# PCB_VIP_Master_BMS_2026.net
KiCad netlist of a schematic drawn in EasyEDA
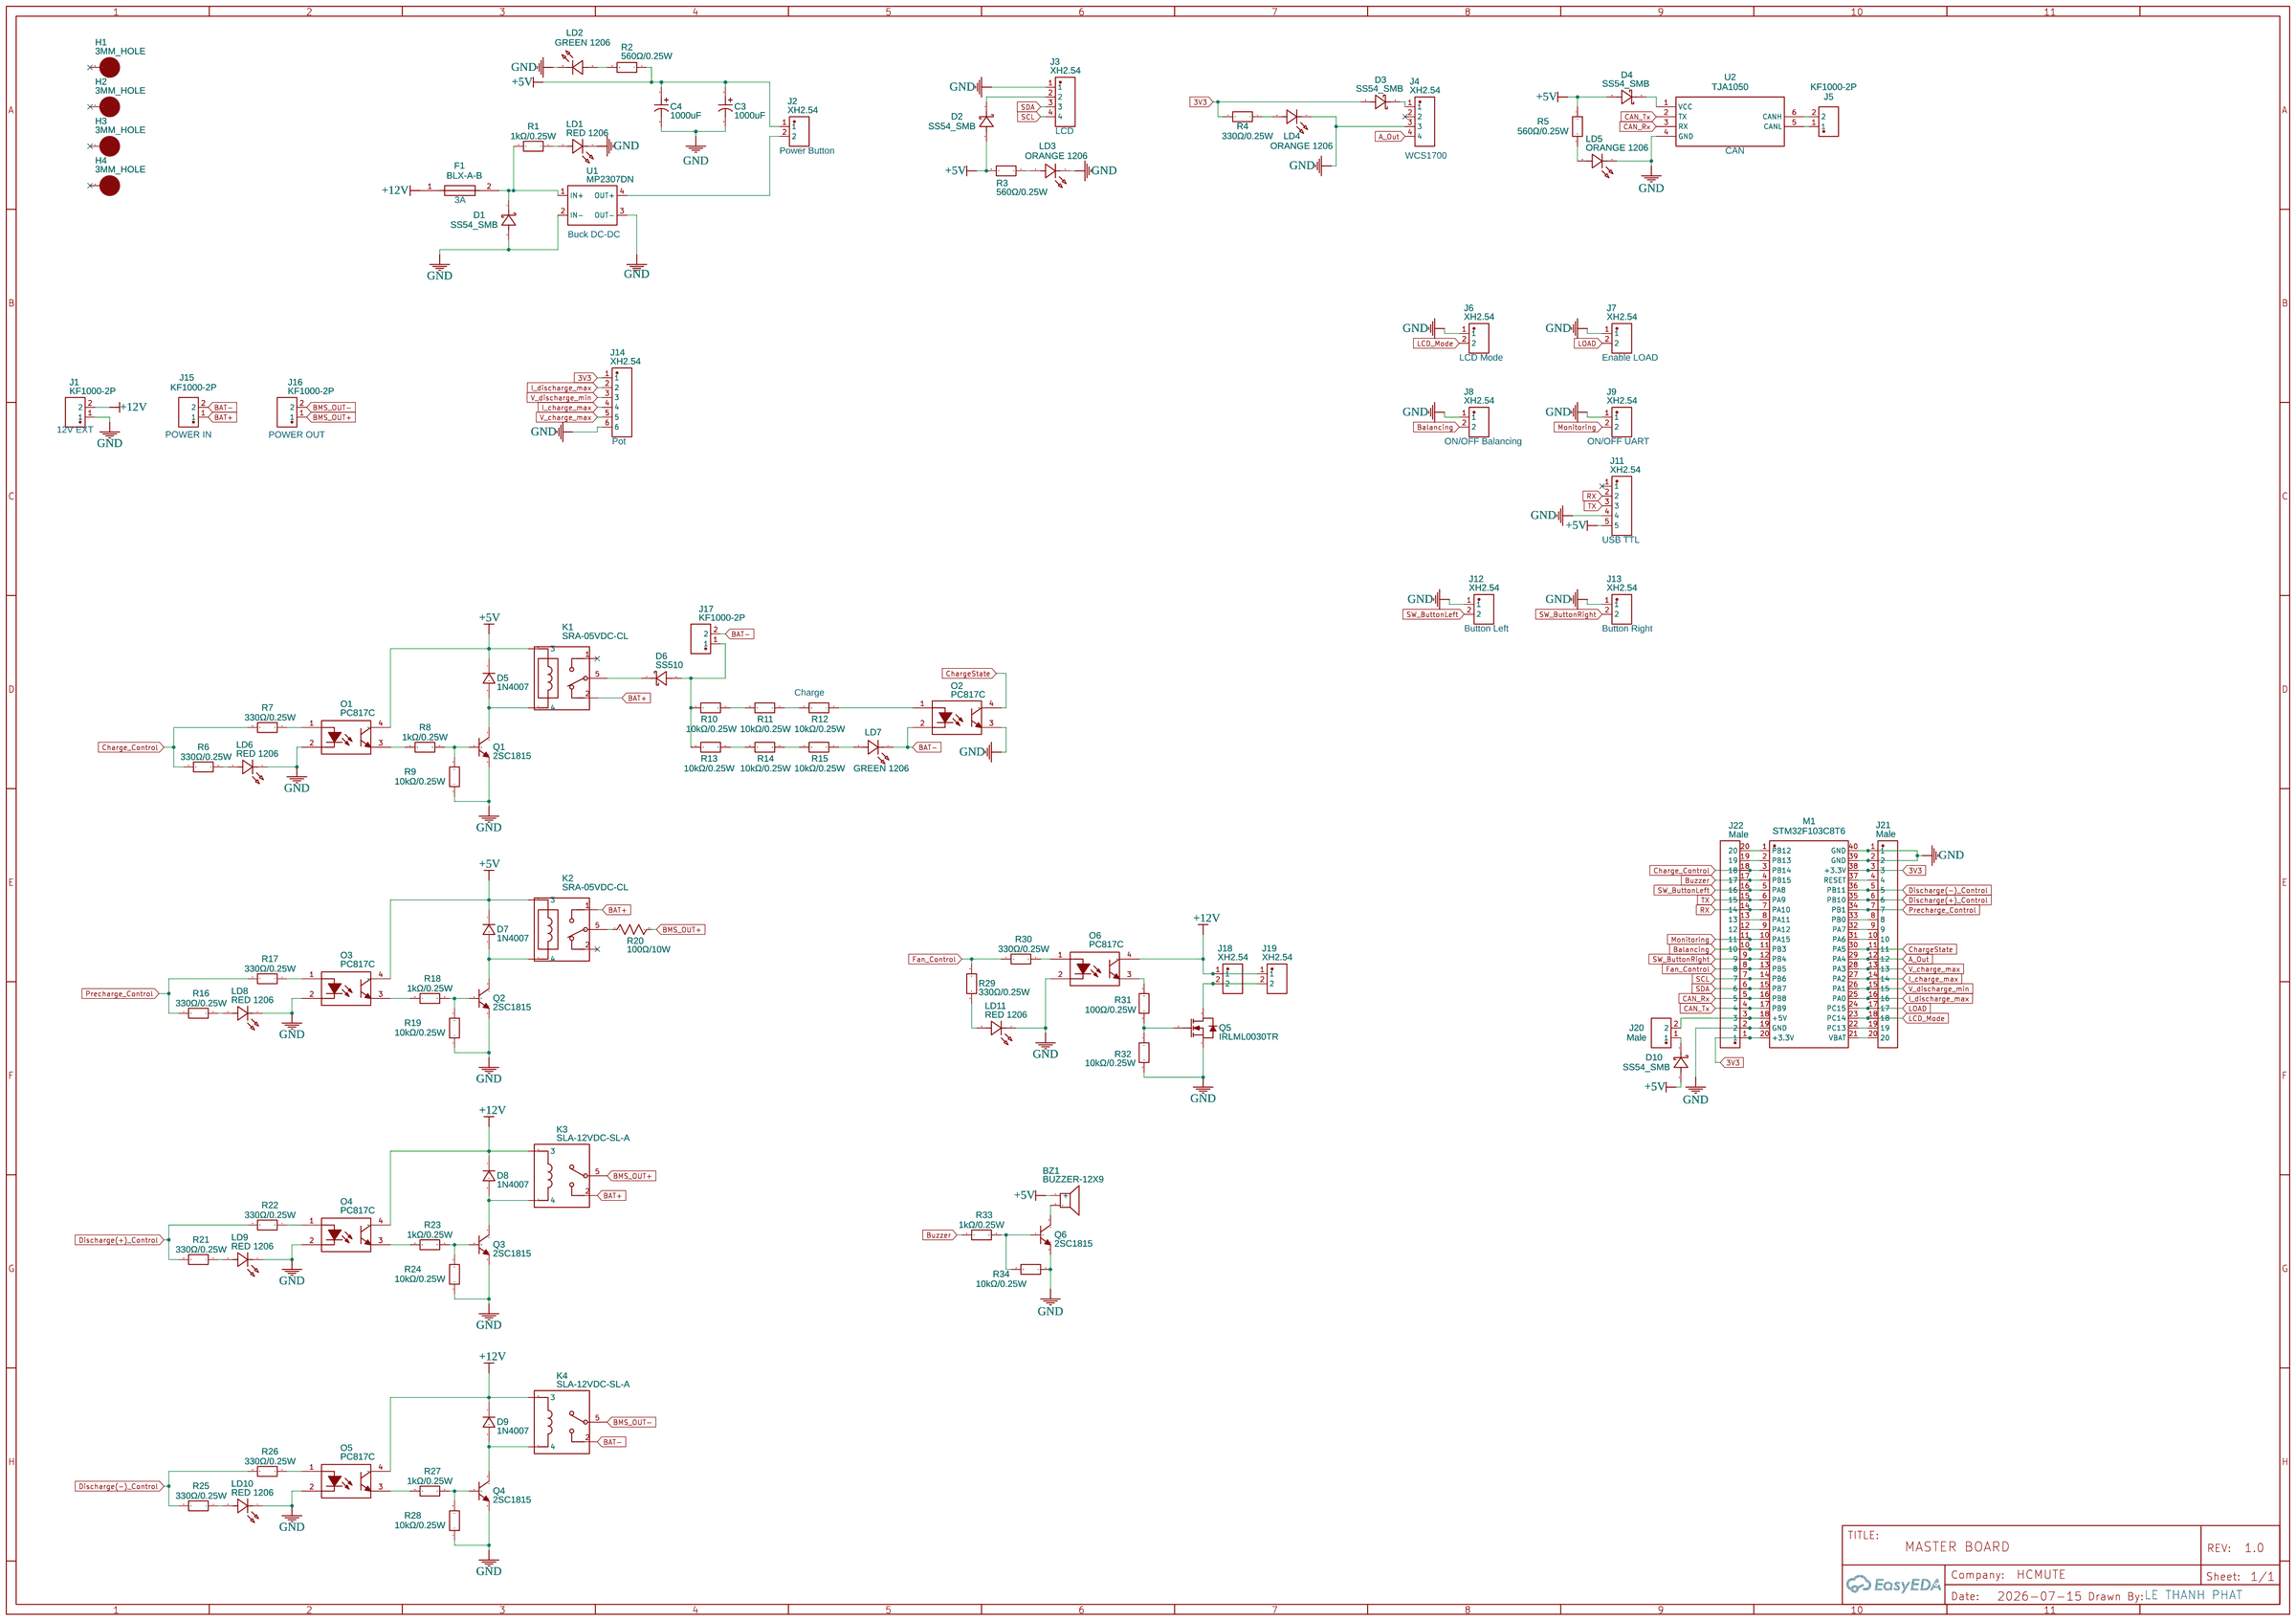
[diagram p0: schematic sheet]

(export (version "E")
  (design (tool "Eeschema 10.0.6"))
  (components
    (comp (ref "BZ1")
      (value "BUZZER-12X9")
      (fields (field (name "Manufacturer Part") "buzzer-12X9"))
      (libsource (lib "") (part "BUZZER-12X9"))
    )
    (comp (ref "C3")
      (value "1000uF")
      (fields
        (field (name "Manufacturer Part") "XT1000UF25V90RV0154")
        (field (name "Manufacturer") "KNSCHA(科尼盛)")
      )
      (libsource (lib "") (part "XT1000UF25V90RV0154"))
    )
    (comp (ref "C4")
      (value "1000uF")
      (fields
        (field (name "Manufacturer Part") "XT1000UF25V90RV0154")
        (field (name "Manufacturer") "KNSCHA(科尼盛)")
      )
      (libsource (lib "") (part "XT1000UF25V90RV0154"))
    )
    (comp (ref "D1")
      (value "SS54_SMB")
      (fields (field (name "Manufacturer Part") "SS54") (field (name "Manufacturer") "HXY MOSFET(华轩阳电子)"))
      (libsource (lib "") (part "SS54_C5200096_2"))
    )
    (comp (ref "D2")
      (value "SS54_SMB")
      (fields (field (name "Manufacturer Part") "SS54") (field (name "Manufacturer") "HXY MOSFET(华轩阳电子)"))
      (libsource (lib "") (part "SS54_C5200096_1"))
    )
    (comp (ref "D3")
      (value "SS54_SMB")
      (fields (field (name "Manufacturer Part") "SS54") (field (name "Manufacturer") "HXY MOSFET(华轩阳电子)"))
      (libsource (lib "") (part "SS54_C5200096"))
    )
    (comp (ref "D4")
      (value "SS54_SMB")
      (fields (field (name "Manufacturer Part") "SS54") (field (name "Manufacturer") "HXY MOSFET(华轩阳电子)"))
      (libsource (lib "") (part "SS54_C5200096"))
    )
    (comp (ref "D5")
      (value "1N4007")
      (fields (field (name "Manufacturer") "SHIKUES(时科)"))
      (libsource (lib "") (part "1N4007_C126233"))
    )
    (comp (ref "D6")
      (value "SS510")
      (fields (field (name "Manufacturer Part") "SS510SMC") (field (name "Manufacturer") "BORN(伯恩半导体)"))
      (libsource (lib "") (part "SS510SMC"))
    )
    (comp (ref "D7")
      (value "1N4007")
      (fields (field (name "Manufacturer") "SHIKUES(时科)"))
      (libsource (lib "") (part "1N4007_C126233"))
    )
    (comp (ref "D8")
      (value "1N4007")
      (fields (field (name "Manufacturer") "SHIKUES(时科)"))
      (libsource (lib "") (part "1N4007_C126233"))
    )
    (comp (ref "D9")
      (value "1N4007")
      (fields (field (name "Manufacturer") "SHIKUES(时科)"))
      (libsource (lib "") (part "1N4007_C126233"))
    )
    (comp (ref "D10")
      (value "SS54_SMB")
      (fields (field (name "Manufacturer Part") "SS54") (field (name "Manufacturer") "HXY MOSFET(华轩阳电子)"))
      (libsource (lib "") (part "SS54_C5200096_1"))
    )
    (comp (ref "F1")
      (value "BLX-A-B")
      (fields (field (name "Manufacturer") "XFCN(兴飞)"))
      (libsource (lib "") (part "BLX-A-B"))
    )
    (comp (ref "H1") (value "3MM_HOLE") (libsource (lib "") (part "3MM_HOLE")))
    (comp (ref "H2") (value "3MM_HOLE") (libsource (lib "") (part "3MM_HOLE")))
    (comp (ref "H3") (value "3MM_HOLE") (libsource (lib "") (part "3MM_HOLE")))
    (comp (ref "H4") (value "3MM_HOLE") (libsource (lib "") (part "3MM_HOLE")))
    (comp (ref "J1") (value "KF1000-2P") (libsource (lib "") (part "KF1000-2P")))
    (comp (ref "J2")
      (value "XH2.54")
      (fields
        (field (name "Manufacturer Part") "ZX-XH2.54-2PZZ-Y")
        (field (name "Manufacturer") "Megastar(兆星)")
      )
      (libsource (lib "") (part "ZX-XH2.54-2PZZ-Y"))
    )
    (comp (ref "J3")
      (value "XH2.54")
      (fields
        (field (name "Manufacturer Part") "ZX-XH2.54-4PZZ")
        (field (name "Manufacturer") "Megastar(兆星)")
      )
      (libsource (lib "") (part "ZX-XH2.54-4PZZ"))
    )
    (comp (ref "J4")
      (value "XH2.54")
      (fields
        (field (name "Manufacturer Part") "ZX-XH2.54-4PZZ")
        (field (name "Manufacturer") "Megastar(兆星)")
      )
      (libsource (lib "") (part "ZX-XH2.54-4PZZ"))
    )
    (comp (ref "J5") (value "KF1000-2P") (libsource (lib "") (part "KF1000-2P_1")))
    (comp (ref "J6")
      (value "XH2.54")
      (fields
        (field (name "Manufacturer Part") "ZX-XH2.54-2PZZ")
        (field (name "Manufacturer") "Megastar(兆星)")
      )
      (libsource (lib "") (part "ZX-XH2.54-2PZZ"))
    )
    (comp (ref "J7")
      (value "XH2.54")
      (fields
        (field (name "Manufacturer Part") "ZX-XH2.54-2PZZ")
        (field (name "Manufacturer") "Megastar(兆星)")
      )
      (libsource (lib "") (part "ZX-XH2.54-2PZZ"))
    )
    (comp (ref "J8")
      (value "XH2.54")
      (fields
        (field (name "Manufacturer Part") "ZX-XH2.54-2PZZ")
        (field (name "Manufacturer") "Megastar(兆星)")
      )
      (libsource (lib "") (part "ZX-XH2.54-2PZZ"))
    )
    (comp (ref "J9")
      (value "XH2.54")
      (fields
        (field (name "Manufacturer Part") "ZX-XH2.54-2PZZ")
        (field (name "Manufacturer") "Megastar(兆星)")
      )
      (libsource (lib "") (part "ZX-XH2.54-2PZZ"))
    )
    (comp (ref "J11")
      (value "XH2.54")
      (fields
        (field (name "Manufacturer Part") "ZX-XH2.54-5PZZ")
        (field (name "Manufacturer") "Megastar(兆星)")
      )
      (libsource (lib "") (part "ZX-XH2.54-5PZZ"))
    )
    (comp (ref "J12")
      (value "XH2.54")
      (fields
        (field (name "Manufacturer Part") "ZX-XH2.54-2PZZ")
        (field (name "Manufacturer") "Megastar(兆星)")
      )
      (libsource (lib "") (part "ZX-XH2.54-2PZZ"))
    )
    (comp (ref "J13")
      (value "XH2.54")
      (fields
        (field (name "Manufacturer Part") "ZX-XH2.54-2PZZ")
        (field (name "Manufacturer") "Megastar(兆星)")
      )
      (libsource (lib "") (part "ZX-XH2.54-2PZZ"))
    )
    (comp (ref "J14")
      (value "XH2.54")
      (fields
        (field (name "Manufacturer Part") "ZX-XH2.54-6PZZ")
        (field (name "Manufacturer") "Megastar(兆星)")
      )
      (libsource (lib "") (part "ZX-XH2.54-6PZZ"))
    )
    (comp (ref "J15") (value "KF1000-2P") (libsource (lib "") (part "KF1000-2P")))
    (comp (ref "J16") (value "KF1000-2P") (libsource (lib "") (part "KF1000-2P")))
    (comp (ref "J17") (value "KF1000-2P") (libsource (lib "") (part "KF1000-2P")))
    (comp (ref "J18")
      (value "XH2.54")
      (fields
        (field (name "Manufacturer Part") "ZX-XH2.54-2PZZ")
        (field (name "Manufacturer") "Megastar(兆星)")
      )
      (libsource (lib "") (part "ZX-XH2.54-2PZZ"))
    )
    (comp (ref "J19")
      (value "XH2.54")
      (fields
        (field (name "Manufacturer Part") "ZX-XH2.54-2PZZ")
        (field (name "Manufacturer") "Megastar(兆星)")
      )
      (libsource (lib "") (part "ZX-XH2.54-2PZZ"))
    )
    (comp (ref "J20")
      (value "Male")
      (fields
        (field (name "Manufacturer Part") "HX PZ2.54-1x2P ZZ")
        (field (name "Manufacturer") "hanxia(韩下)")
      )
      (libsource (lib "") (part "HX PZ2.54-1X2P ZZ"))
    )
    (comp (ref "J21")
      (value "Male")
      (fields
        (field (name "Manufacturer Part") "HX PZ2.54-1x20P ZZ")
        (field (name "Manufacturer") "hanxia(韩下)")
      )
      (libsource (lib "") (part "HX PZ2.54-1X20P ZZ"))
    )
    (comp (ref "J22")
      (value "Male")
      (fields
        (field (name "Manufacturer Part") "HX PZ2.54-1x20P ZZ")
        (field (name "Manufacturer") "hanxia(韩下)")
      )
      (libsource (lib "") (part "HX PZ2.54-1X20P ZZ_1"))
    )
    (comp (ref "K1")
      (value "SRA-05VDC-CL")
      (fields (field (name "Manufacturer") "松乐"))
      (libsource (lib "") (part "SRA-05VDC-CL"))
    )
    (comp (ref "K2")
      (value "SRA-05VDC-CL")
      (fields (field (name "Manufacturer") "松乐"))
      (libsource (lib "") (part "SRA-05VDC-CL"))
    )
    (comp (ref "K3")
      (value "SLA-12VDC-SL-A")
      (fields (field (name "Manufacturer") "松乐"))
      (libsource (lib "") (part "SLA-12VDC-SL-A"))
    )
    (comp (ref "K4")
      (value "SLA-12VDC-SL-A")
      (fields (field (name "Manufacturer") "松乐"))
      (libsource (lib "") (part "SLA-12VDC-SL-A"))
    )
    (comp (ref "LD1")
      (value "RED 1206")
      (fields
        (field (name "Manufacturer Part") "TJ-S3216EX9T5ALC2R-A5")
        (field (name "Manufacturer") "TOGIALED(统佳)")
      )
      (libsource (lib "") (part "TJ-S3216EX9T5ALC2R-A5_2"))
    )
    (comp (ref "LD2")
      (value "GREEN 1206")
      (fields
        (field (name "Manufacturer Part") "TJ-S3216EX9T5ALC2R-A5")
        (field (name "Manufacturer") "TOGIALED(统佳)")
      )
      (libsource (lib "") (part "TJ-S3216EX9T5ALC2R-A5"))
    )
    (comp (ref "LD3")
      (value "ORANGE 1206")
      (fields
        (field (name "Manufacturer Part") "TJ-S3216EX9T5ALC2R-A5")
        (field (name "Manufacturer") "TOGIALED(统佳)")
      )
      (libsource (lib "") (part "TJ-S3216EX9T5ALC2R-A5_1"))
    )
    (comp (ref "LD4")
      (value "ORANGE 1206")
      (fields
        (field (name "Manufacturer Part") "TJ-S3216EX9T5ALC2R-A5")
        (field (name "Manufacturer") "TOGIALED(统佳)")
      )
      (libsource (lib "") (part "TJ-S3216EX9T5ALC2R-A5_1"))
    )
    (comp (ref "LD5")
      (value "ORANGE 1206")
      (fields
        (field (name "Manufacturer Part") "TJ-S3216EX9T5ALC2R-A5")
        (field (name "Manufacturer") "TOGIALED(统佳)")
      )
      (libsource (lib "") (part "TJ-S3216EX9T5ALC2R-A5_1"))
    )
    (comp (ref "LD6")
      (value "RED 1206")
      (fields
        (field (name "Manufacturer Part") "TJ-S3216EX9T5ALC2R-A5")
        (field (name "Manufacturer") "TOGIALED(统佳)")
      )
      (libsource (lib "") (part "TJ-S3216EX9T5ALC2R-A5_1"))
    )
    (comp (ref "LD7")
      (value "GREEN 1206")
      (fields
        (field (name "Manufacturer Part") "TJ-S3216EX9T5ALC2R-A5")
        (field (name "Manufacturer") "TOGIALED(统佳)")
      )
      (libsource (lib "") (part "TJ-S3216EX9T5ALC2R-A5_2"))
    )
    (comp (ref "LD8")
      (value "RED 1206")
      (fields
        (field (name "Manufacturer Part") "TJ-S3216EX9T5ALC2R-A5")
        (field (name "Manufacturer") "TOGIALED(统佳)")
      )
      (libsource (lib "") (part "TJ-S3216EX9T5ALC2R-A5_1"))
    )
    (comp (ref "LD9")
      (value "RED 1206")
      (fields
        (field (name "Manufacturer Part") "TJ-S3216EX9T5ALC2R-A5")
        (field (name "Manufacturer") "TOGIALED(统佳)")
      )
      (libsource (lib "") (part "TJ-S3216EX9T5ALC2R-A5_1"))
    )
    (comp (ref "LD10")
      (value "RED 1206")
      (fields
        (field (name "Manufacturer Part") "TJ-S3216EX9T5ALC2R-A5")
        (field (name "Manufacturer") "TOGIALED(统佳)")
      )
      (libsource (lib "") (part "TJ-S3216EX9T5ALC2R-A5_1"))
    )
    (comp (ref "LD11")
      (value "RED 1206")
      (fields
        (field (name "Manufacturer Part") "TJ-S3216EX9T5ALC2R-A5")
        (field (name "Manufacturer") "TOGIALED(统佳)")
      )
      (libsource (lib "") (part "TJ-S3216EX9T5ALC2R-A5_2"))
    )
    (comp (ref "M1")
      (value "STM32F103C8T6")
      (fields
        (field (name "Manufacturer Part") "LCKFB-DKX-STM32F103C8T6")
        (field (name "Manufacturer") "立创开发板")
      )
      (libsource (lib "") (part "LCKFB-DKX-STM32F103C8T6"))
    )
    (comp (ref "O1")
      (value "PC817C")
      (fields (field (name "Manufacturer") "JSMSEMI(杰盛微)"))
      (libsource (lib "") (part "PC817C_C22447129"))
    )
    (comp (ref "O2")
      (value "PC817C")
      (fields (field (name "Manufacturer") "JSMSEMI(杰盛微)"))
      (libsource (lib "") (part "PC817C_C22447129"))
    )
    (comp (ref "O3")
      (value "PC817C")
      (fields (field (name "Manufacturer") "JSMSEMI(杰盛微)"))
      (libsource (lib "") (part "PC817C_C22447129"))
    )
    (comp (ref "O4")
      (value "PC817C")
      (fields (field (name "Manufacturer") "JSMSEMI(杰盛微)"))
      (libsource (lib "") (part "PC817C_C22447129"))
    )
    (comp (ref "O5")
      (value "PC817C")
      (fields (field (name "Manufacturer") "JSMSEMI(杰盛微)"))
      (libsource (lib "") (part "PC817C_C22447129"))
    )
    (comp (ref "O6")
      (value "PC817C")
      (fields (field (name "Manufacturer") "JSMSEMI(杰盛微)"))
      (libsource (lib "") (part "PC817C_C22447129"))
    )
    (comp (ref "Q1")
      (value "2SC1815")
      (fields (field (name "Manufacturer") "MSKSEMI(美森科)"))
      (libsource (lib "") (part "2SC1815_C2914411"))
    )
    (comp (ref "Q2")
      (value "2SC1815")
      (fields (field (name "Manufacturer") "MSKSEMI(美森科)"))
      (libsource (lib "") (part "2SC1815_C2914411"))
    )
    (comp (ref "Q3")
      (value "2SC1815")
      (fields (field (name "Manufacturer") "MSKSEMI(美森科)"))
      (libsource (lib "") (part "2SC1815_C2914411"))
    )
    (comp (ref "Q4")
      (value "2SC1815")
      (fields (field (name "Manufacturer") "MSKSEMI(美森科)"))
      (libsource (lib "") (part "2SC1815_C2914411"))
    )
    (comp (ref "Q5")
      (value "IRLML0030TR")
      (fields
        (field (name "Manufacturer Part") "IRLML0030TRPBF-G")
        (field (name "Manufacturer") "TECH PUBLIC(台舟)")
      )
      (libsource (lib "") (part "IRLML0030TRPBF-G"))
    )
    (comp (ref "Q6")
      (value "2SC1815")
      (fields (field (name "Manufacturer") "MSKSEMI(美森科)"))
      (libsource (lib "") (part "2SC1815_C2914411"))
    )
    (comp (ref "R1")
      (value "1kΩ/0.25W")
      (fields
        (field (name "Manufacturer Part") "HoAR1206-1/4W-1KR-1%-TCR50")
        (field (name "Manufacturer") "Milliohm(毫欧)")
      )
      (libsource (lib "") (part "HOAR1206-1/4W-1KR-1%-TCR50"))
    )
    (comp (ref "R2")
      (value "560Ω/0.25W")
      (fields
        (field (name "Manufacturer Part") "HoAR1206-1/4W-1KR-1%-TCR50")
        (field (name "Manufacturer") "Milliohm(毫欧)")
      )
      (libsource (lib "") (part "HOAR1206-1/4W-1KR-1%-TCR50"))
    )
    (comp (ref "R3")
      (value "560Ω/0.25W")
      (fields
        (field (name "Manufacturer Part") "HoAR1206-1/4W-1KR-1%-TCR50")
        (field (name "Manufacturer") "Milliohm(毫欧)")
      )
      (libsource (lib "") (part "HOAR1206-1/4W-1KR-1%-TCR50"))
    )
    (comp (ref "R4")
      (value "330Ω/0.25W")
      (fields
        (field (name "Manufacturer Part") "HoAR1206-1/4W-1KR-1%-TCR50")
        (field (name "Manufacturer") "Milliohm(毫欧)")
      )
      (libsource (lib "") (part "HOAR1206-1/4W-1KR-1%-TCR50"))
    )
    (comp (ref "R5")
      (value "560Ω/0.25W")
      (fields
        (field (name "Manufacturer Part") "HoAR1206-1/4W-1KR-1%-TCR50")
        (field (name "Manufacturer") "Milliohm(毫欧)")
      )
      (libsource (lib "") (part "HOAR1206-1/4W-1KR-1%-TCR50_1"))
    )
    (comp (ref "R6")
      (value "330Ω/0.25W")
      (fields
        (field (name "Manufacturer Part") "HoAR1206-1/4W-1KR-1%-TCR50")
        (field (name "Manufacturer") "Milliohm(毫欧)")
      )
      (libsource (lib "") (part "HOAR1206-1/4W-1KR-1%-TCR50"))
    )
    (comp (ref "R7")
      (value "330Ω/0.25W")
      (fields
        (field (name "Manufacturer Part") "HoAR1206-1/4W-1KR-1%-TCR50")
        (field (name "Manufacturer") "Milliohm(毫欧)")
      )
      (libsource (lib "") (part "HOAR1206-1/4W-1KR-1%-TCR50"))
    )
    (comp (ref "R8")
      (value "1kΩ/0.25W")
      (fields
        (field (name "Manufacturer Part") "HoAR1206-1/4W-1KR-1%-TCR50")
        (field (name "Manufacturer") "Milliohm(毫欧)")
      )
      (libsource (lib "") (part "HOAR1206-1/4W-1KR-1%-TCR50"))
    )
    (comp (ref "R9")
      (value "10kΩ/0.25W")
      (fields
        (field (name "Manufacturer Part") "HoAR1206-1/4W-1KR-1%-TCR50")
        (field (name "Manufacturer") "Milliohm(毫欧)")
      )
      (libsource (lib "") (part "HOAR1206-1/4W-1KR-1%-TCR50_2"))
    )
    (comp (ref "R10")
      (value "10kΩ/0.25W")
      (fields
        (field (name "Manufacturer Part") "HoAR1206-1/4W-1KR-1%-TCR50")
        (field (name "Manufacturer") "Milliohm(毫欧)")
      )
      (libsource (lib "") (part "HOAR1206-1/4W-1KR-1%-TCR50"))
    )
    (comp (ref "R11")
      (value "10kΩ/0.25W")
      (fields
        (field (name "Manufacturer Part") "HoAR1206-1/4W-1KR-1%-TCR50")
        (field (name "Manufacturer") "Milliohm(毫欧)")
      )
      (libsource (lib "") (part "HOAR1206-1/4W-1KR-1%-TCR50"))
    )
    (comp (ref "R12")
      (value "10kΩ/0.25W")
      (fields
        (field (name "Manufacturer Part") "HoAR1206-1/4W-1KR-1%-TCR50")
        (field (name "Manufacturer") "Milliohm(毫欧)")
      )
      (libsource (lib "") (part "HOAR1206-1/4W-1KR-1%-TCR50"))
    )
    (comp (ref "R13")
      (value "10kΩ/0.25W")
      (fields
        (field (name "Manufacturer Part") "HoAR1206-1/4W-1KR-1%-TCR50")
        (field (name "Manufacturer") "Milliohm(毫欧)")
      )
      (libsource (lib "") (part "HOAR1206-1/4W-1KR-1%-TCR50"))
    )
    (comp (ref "R14")
      (value "10kΩ/0.25W")
      (fields
        (field (name "Manufacturer Part") "HoAR1206-1/4W-1KR-1%-TCR50")
        (field (name "Manufacturer") "Milliohm(毫欧)")
      )
      (libsource (lib "") (part "HOAR1206-1/4W-1KR-1%-TCR50"))
    )
    (comp (ref "R15")
      (value "10kΩ/0.25W")
      (fields
        (field (name "Manufacturer Part") "HoAR1206-1/4W-1KR-1%-TCR50")
        (field (name "Manufacturer") "Milliohm(毫欧)")
      )
      (libsource (lib "") (part "HOAR1206-1/4W-1KR-1%-TCR50"))
    )
    (comp (ref "R16")
      (value "330Ω/0.25W")
      (fields
        (field (name "Manufacturer Part") "HoAR1206-1/4W-1KR-1%-TCR50")
        (field (name "Manufacturer") "Milliohm(毫欧)")
      )
      (libsource (lib "") (part "HOAR1206-1/4W-1KR-1%-TCR50"))
    )
    (comp (ref "R17")
      (value "330Ω/0.25W")
      (fields
        (field (name "Manufacturer Part") "HoAR1206-1/4W-1KR-1%-TCR50")
        (field (name "Manufacturer") "Milliohm(毫欧)")
      )
      (libsource (lib "") (part "HOAR1206-1/4W-1KR-1%-TCR50"))
    )
    (comp (ref "R18")
      (value "1kΩ/0.25W")
      (fields
        (field (name "Manufacturer Part") "HoAR1206-1/4W-1KR-1%-TCR50")
        (field (name "Manufacturer") "Milliohm(毫欧)")
      )
      (libsource (lib "") (part "HOAR1206-1/4W-1KR-1%-TCR50"))
    )
    (comp (ref "R19")
      (value "10kΩ/0.25W")
      (fields
        (field (name "Manufacturer Part") "HoAR1206-1/4W-1KR-1%-TCR50")
        (field (name "Manufacturer") "Milliohm(毫欧)")
      )
      (libsource (lib "") (part "HOAR1206-1/4W-1KR-1%-TCR50_2"))
    )
    (comp (ref "R20")
      (value "100Ω/10W")
      (libsource (lib "") (part "DAYTON AUDIO 4.7 OHM 10W PRECISION AUDIO GRADE RESISTOR COPY"))
    )
    (comp (ref "R21")
      (value "330Ω/0.25W")
      (fields
        (field (name "Manufacturer Part") "HoAR1206-1/4W-1KR-1%-TCR50")
        (field (name "Manufacturer") "Milliohm(毫欧)")
      )
      (libsource (lib "") (part "HOAR1206-1/4W-1KR-1%-TCR50"))
    )
    (comp (ref "R22")
      (value "330Ω/0.25W")
      (fields
        (field (name "Manufacturer Part") "HoAR1206-1/4W-1KR-1%-TCR50")
        (field (name "Manufacturer") "Milliohm(毫欧)")
      )
      (libsource (lib "") (part "HOAR1206-1/4W-1KR-1%-TCR50"))
    )
    (comp (ref "R23")
      (value "1kΩ/0.25W")
      (fields
        (field (name "Manufacturer Part") "HoAR1206-1/4W-1KR-1%-TCR50")
        (field (name "Manufacturer") "Milliohm(毫欧)")
      )
      (libsource (lib "") (part "HOAR1206-1/4W-1KR-1%-TCR50"))
    )
    (comp (ref "R24")
      (value "10kΩ/0.25W")
      (fields
        (field (name "Manufacturer Part") "HoAR1206-1/4W-1KR-1%-TCR50")
        (field (name "Manufacturer") "Milliohm(毫欧)")
      )
      (libsource (lib "") (part "HOAR1206-1/4W-1KR-1%-TCR50_2"))
    )
    (comp (ref "R25")
      (value "330Ω/0.25W")
      (fields
        (field (name "Manufacturer Part") "HoAR1206-1/4W-1KR-1%-TCR50")
        (field (name "Manufacturer") "Milliohm(毫欧)")
      )
      (libsource (lib "") (part "HOAR1206-1/4W-1KR-1%-TCR50"))
    )
    (comp (ref "R26")
      (value "330Ω/0.25W")
      (fields
        (field (name "Manufacturer Part") "HoAR1206-1/4W-1KR-1%-TCR50")
        (field (name "Manufacturer") "Milliohm(毫欧)")
      )
      (libsource (lib "") (part "HOAR1206-1/4W-1KR-1%-TCR50"))
    )
    (comp (ref "R27")
      (value "1kΩ/0.25W")
      (fields
        (field (name "Manufacturer Part") "HoAR1206-1/4W-1KR-1%-TCR50")
        (field (name "Manufacturer") "Milliohm(毫欧)")
      )
      (libsource (lib "") (part "HOAR1206-1/4W-1KR-1%-TCR50"))
    )
    (comp (ref "R28")
      (value "10kΩ/0.25W")
      (fields
        (field (name "Manufacturer Part") "HoAR1206-1/4W-1KR-1%-TCR50")
        (field (name "Manufacturer") "Milliohm(毫欧)")
      )
      (libsource (lib "") (part "HOAR1206-1/4W-1KR-1%-TCR50_2"))
    )
    (comp (ref "R29")
      (value "330Ω/0.25W")
      (fields
        (field (name "Manufacturer Part") "HoAR1206-1/4W-1KR-1%-TCR50")
        (field (name "Manufacturer") "Milliohm(毫欧)")
      )
      (libsource (lib "") (part "HOAR1206-1/4W-1KR-1%-TCR50_2"))
    )
    (comp (ref "R30")
      (value "330Ω/0.25W")
      (fields
        (field (name "Manufacturer Part") "HoAR1206-1/4W-1KR-1%-TCR50")
        (field (name "Manufacturer") "Milliohm(毫欧)")
      )
      (libsource (lib "") (part "HOAR1206-1/4W-1KR-1%-TCR50"))
    )
    (comp (ref "R31")
      (value "100Ω/0.25W")
      (fields
        (field (name "Manufacturer Part") "HoAR1206-1/4W-1KR-1%-TCR50")
        (field (name "Manufacturer") "Milliohm(毫欧)")
      )
      (libsource (lib "") (part "HOAR1206-1/4W-1KR-1%-TCR50_1"))
    )
    (comp (ref "R32")
      (value "10kΩ/0.25W")
      (fields
        (field (name "Manufacturer Part") "HoAR1206-1/4W-1KR-1%-TCR50")
        (field (name "Manufacturer") "Milliohm(毫欧)")
      )
      (libsource (lib "") (part "HOAR1206-1/4W-1KR-1%-TCR50_1"))
    )
    (comp (ref "R33")
      (value "1kΩ/0.25W")
      (fields
        (field (name "Manufacturer Part") "HoAR1206-1/4W-1KR-1%-TCR50")
        (field (name "Manufacturer") "Milliohm(毫欧)")
      )
      (libsource (lib "") (part "HOAR1206-1/4W-1KR-1%-TCR50"))
    )
    (comp (ref "R34")
      (value "10kΩ/0.25W")
      (fields
        (field (name "Manufacturer Part") "HoAR1206-1/4W-1KR-1%-TCR50")
        (field (name "Manufacturer") "Milliohm(毫欧)")
      )
      (libsource (lib "") (part "HOAR1206-1/4W-1KR-1%-TCR50"))
    )
    (comp (ref "U1") (value "MP2307DN") (libsource (lib "") (part "MP2307DN")))
    (comp (ref "U2") (value "TJA1050") (libsource (lib "") (part "CANBUSTJA1050 COPY")))
  )
  (nets
    (net (code "1") (name "+5V") (class "Default")
      (node (ref "BZ1") (pin "1") (pinfunction "+_1") (pintype "unspecified"))
      (node (ref "C3") (pin "1") (pinfunction "1_1") (pintype "input"))
      (node (ref "C4") (pin "1") (pinfunction "1_1") (pintype "input"))
      (node (ref "D10") (pin "2") (pinfunction "2_2") (pintype "unspecified"))
      (node (ref "D2") (pin "2") (pinfunction "2_2") (pintype "unspecified"))
      (node (ref "D4") (pin "2") (pinfunction "2_2") (pintype "unspecified"))
      (node (ref "D5") (pin "1") (pinfunction "1_1") (pintype "unspecified"))
      (node (ref "D7") (pin "1") (pinfunction "1_1") (pintype "unspecified"))
      (node (ref "J11") (pin "5") (pinfunction "5_5") (pintype "unspecified"))
      (node (ref "J2") (pin "1") (pinfunction "1_1") (pintype "unspecified"))
      (node (ref "K1") (pin "3") (pinfunction "3_3") (pintype "unspecified"))
      (node (ref "K2") (pin "3") (pinfunction "3_3") (pintype "unspecified"))
      (node (ref "O1") (pin "4") (pinfunction "COL_4") (pintype "unspecified"))
      (node (ref "O3") (pin "4") (pinfunction "COL_4") (pintype "unspecified"))
      (node (ref "R2") (pin "1") (pinfunction "1_1") (pintype "unspecified"))
      (node (ref "R3") (pin "2") (pinfunction "2_2") (pintype "unspecified"))
      (node (ref "R5") (pin "1") (pinfunction "1_1") (pintype "unspecified"))
    )
    (net (code "2") (name "+12V") (class "Default")
      (node (ref "D8") (pin "1") (pinfunction "1_1") (pintype "unspecified"))
      (node (ref "D9") (pin "1") (pinfunction "1_1") (pintype "unspecified"))
      (node (ref "F1") (pin "1") (pinfunction "1_1") (pintype "unspecified"))
      (node (ref "J1") (pin "2") (pinfunction "2_2") (pintype "unspecified"))
      (node (ref "J18") (pin "1") (pinfunction "1_1") (pintype "unspecified"))
      (node (ref "J19") (pin "1") (pinfunction "1_1") (pintype "unspecified"))
      (node (ref "K3") (pin "3") (pinfunction "3_3") (pintype "unspecified"))
      (node (ref "K4") (pin "3") (pinfunction "3_3") (pintype "unspecified"))
      (node (ref "O4") (pin "4") (pinfunction "COL_4") (pintype "unspecified"))
      (node (ref "O5") (pin "4") (pinfunction "COL_4") (pintype "unspecified"))
      (node (ref "O6") (pin "4") (pinfunction "COL_4") (pintype "unspecified"))
    )
    (net (code "3") (name "3V3") (class "Default")
      (node (ref "D3") (pin "2") (pinfunction "2_2") (pintype "unspecified"))
      (node (ref "J14") (pin "1") (pinfunction "1_1") (pintype "unspecified"))
      (node (ref "J21") (pin "3") (pinfunction "3_3") (pintype "unspecified"))
      (node (ref "J22") (pin "1") (pinfunction "1_1") (pintype "unspecified"))
      (node (ref "M1") (pin "20") (pinfunction "+3.3V_20") (pintype "unspecified"))
      (node (ref "M1") (pin "38") (pinfunction "+3.3V_38") (pintype "unspecified"))
      (node (ref "R4") (pin "2") (pinfunction "2_2") (pintype "unspecified"))
    )
    (net (code "4") (name "A_Out") (class "Default")
      (node (ref "J21") (pin "12") (pinfunction "12_12") (pintype "unspecified"))
      (node (ref "J4") (pin "4") (pinfunction "4_4") (pintype "unspecified"))
      (node (ref "M1") (pin "29") (pinfunction "PA4_29") (pintype "unspecified"))
    )
    (net (code "5") (name "BAT+") (class "Default")
      (node (ref "J15") (pin "1") (pinfunction "1_1") (pintype "unspecified"))
      (node (ref "K1") (pin "2") (pinfunction "2_2") (pintype "unspecified"))
      (node (ref "K2") (pin "1") (pinfunction "1_1") (pintype "unspecified"))
      (node (ref "K3") (pin "2") (pinfunction "2_2") (pintype "unspecified"))
    )
    (net (code "6") (name "BAT-") (class "Default")
      (node (ref "J15") (pin "2") (pinfunction "2_2") (pintype "unspecified"))
      (node (ref "J17") (pin "2") (pinfunction "2_2") (pintype "unspecified"))
      (node (ref "K4") (pin "2") (pinfunction "2_2") (pintype "unspecified"))
      (node (ref "LD7") (pin "1") (pinfunction "C_1") (pintype "unspecified"))
      (node (ref "O2") (pin "2") (pinfunction "CAT_2") (pintype "unspecified"))
    )
    (net (code "7") (name "BMS_OUT+") (class "Default")
      (node (ref "J16") (pin "1") (pinfunction "1_1") (pintype "unspecified"))
      (node (ref "K3") (pin "5") (pinfunction "5_5") (pintype "unspecified"))
      (node (ref "R20") (pin "2") (pinfunction "2_2") (pintype "unspecified"))
    )
    (net (code "8") (name "BMS_OUT-") (class "Default")
      (node (ref "J16") (pin "2") (pinfunction "2_2") (pintype "unspecified"))
      (node (ref "K4") (pin "5") (pinfunction "5_5") (pintype "unspecified"))
    )
    (net (code "9") (name "Balancing") (class "Default")
      (node (ref "J22") (pin "10") (pinfunction "10_10") (pintype "unspecified"))
      (node (ref "J8") (pin "2") (pinfunction "2_2") (pintype "unspecified"))
      (node (ref "M1") (pin "11") (pinfunction "PB3_11") (pintype "unspecified"))
    )
    (net (code "10") (name "Buzzer") (class "Default")
      (node (ref "J22") (pin "17") (pinfunction "17_17") (pintype "unspecified"))
      (node (ref "M1") (pin "4") (pinfunction "PB15_4") (pintype "unspecified"))
      (node (ref "R33") (pin "2") (pinfunction "2_2") (pintype "unspecified"))
    )
    (net (code "11") (name "CAN_Rx") (class "Default")
      (node (ref "J22") (pin "5") (pinfunction "5_5") (pintype "unspecified"))
      (node (ref "M1") (pin "16") (pinfunction "PB8_16") (pintype "unspecified"))
      (node (ref "U2") (pin "3") (pinfunction "RX_3") (pintype "unspecified"))
    )
    (net (code "12") (name "CAN_Tx") (class "Default")
      (node (ref "J22") (pin "4") (pinfunction "4_4") (pintype "unspecified"))
      (node (ref "M1") (pin "17") (pinfunction "PB9_17") (pintype "unspecified"))
      (node (ref "U2") (pin "2") (pinfunction "TX_2") (pintype "unspecified"))
    )
    (net (code "13") (name "ChargeState") (class "Default")
      (node (ref "J21") (pin "11") (pinfunction "11_11") (pintype "unspecified"))
      (node (ref "M1") (pin "30") (pinfunction "PA5_30") (pintype "unspecified"))
      (node (ref "O2") (pin "4") (pinfunction "COL_4") (pintype "unspecified"))
    )
    (net (code "14") (name "Charge_Control") (class "Default")
      (node (ref "J22") (pin "18") (pinfunction "18_18") (pintype "unspecified"))
      (node (ref "M1") (pin "3") (pinfunction "PB14_3") (pintype "unspecified"))
      (node (ref "R6") (pin "2") (pinfunction "2_2") (pintype "unspecified"))
      (node (ref "R7") (pin "2") (pinfunction "2_2") (pintype "unspecified"))
    )
    (net (code "15") (name "Discharge(+)_Control") (class "Default")
      (node (ref "J21") (pin "6") (pinfunction "6_6") (pintype "unspecified"))
      (node (ref "M1") (pin "35") (pinfunction "PB10_35") (pintype "unspecified"))
      (node (ref "R21") (pin "2") (pinfunction "2_2") (pintype "unspecified"))
      (node (ref "R22") (pin "2") (pinfunction "2_2") (pintype "unspecified"))
    )
    (net (code "16") (name "Discharge(-)_Control") (class "Default")
      (node (ref "J21") (pin "5") (pinfunction "5_5") (pintype "unspecified"))
      (node (ref "M1") (pin "36") (pinfunction "PB11_36") (pintype "unspecified"))
      (node (ref "R25") (pin "2") (pinfunction "2_2") (pintype "unspecified"))
      (node (ref "R26") (pin "2") (pinfunction "2_2") (pintype "unspecified"))
    )
    (net (code "17") (name "Fan_Control") (class "Default")
      (node (ref "J22") (pin "8") (pinfunction "8_8") (pintype "unspecified"))
      (node (ref "M1") (pin "13") (pinfunction "PB5_13") (pintype "unspecified"))
      (node (ref "R29") (pin "2") (pinfunction "2_2") (pintype "unspecified"))
      (node (ref "R30") (pin "2") (pinfunction "2_2") (pintype "unspecified"))
    )
    (net (code "18") (name "GND") (class "Default")
      (node (ref "C3") (pin "2") (pinfunction "2_2") (pintype "input"))
      (node (ref "C4") (pin "2") (pinfunction "2_2") (pintype "input"))
      (node (ref "D1") (pin "2") (pinfunction "2_2") (pintype "unspecified"))
      (node (ref "J1") (pin "1") (pinfunction "1_1") (pintype "unspecified"))
      (node (ref "J11") (pin "4") (pinfunction "4_4") (pintype "unspecified"))
      (node (ref "J12") (pin "1") (pinfunction "1_1") (pintype "unspecified"))
      (node (ref "J13") (pin "1") (pinfunction "1_1") (pintype "unspecified"))
      (node (ref "J14") (pin "6") (pinfunction "6_6") (pintype "unspecified"))
      (node (ref "J21") (pin "1") (pinfunction "1_1") (pintype "unspecified"))
      (node (ref "J21") (pin "2") (pinfunction "2_2") (pintype "unspecified"))
      (node (ref "J22") (pin "2") (pinfunction "2_2") (pintype "unspecified"))
      (node (ref "J3") (pin "1") (pinfunction "1_1") (pintype "unspecified"))
      (node (ref "J4") (pin "3") (pinfunction "3_3") (pintype "unspecified"))
      (node (ref "J6") (pin "1") (pinfunction "1_1") (pintype "unspecified"))
      (node (ref "J7") (pin "1") (pinfunction "1_1") (pintype "unspecified"))
      (node (ref "J8") (pin "1") (pinfunction "1_1") (pintype "unspecified"))
      (node (ref "J9") (pin "1") (pinfunction "1_1") (pintype "unspecified"))
      (node (ref "LD1") (pin "1") (pinfunction "C_1") (pintype "unspecified"))
      (node (ref "LD10") (pin "1") (pinfunction "C_1") (pintype "unspecified"))
      (node (ref "LD11") (pin "1") (pinfunction "C_1") (pintype "unspecified"))
      (node (ref "LD2") (pin "1") (pinfunction "C_1") (pintype "unspecified"))
      (node (ref "LD3") (pin "1") (pinfunction "C_1") (pintype "unspecified"))
      (node (ref "LD4") (pin "1") (pinfunction "C_1") (pintype "unspecified"))
      (node (ref "LD5") (pin "1") (pinfunction "C_1") (pintype "unspecified"))
      (node (ref "LD6") (pin "1") (pinfunction "C_1") (pintype "unspecified"))
      (node (ref "LD8") (pin "1") (pinfunction "C_1") (pintype "unspecified"))
      (node (ref "LD9") (pin "1") (pinfunction "C_1") (pintype "unspecified"))
      (node (ref "M1") (pin "19") (pinfunction "GND_19") (pintype "unspecified"))
      (node (ref "M1") (pin "39") (pinfunction "GND_39") (pintype "unspecified"))
      (node (ref "M1") (pin "40") (pinfunction "GND_40") (pintype "unspecified"))
      (node (ref "O1") (pin "2") (pinfunction "CAT_2") (pintype "unspecified"))
      (node (ref "O2") (pin "3") (pinfunction "EM_3") (pintype "unspecified"))
      (node (ref "O3") (pin "2") (pinfunction "CAT_2") (pintype "unspecified"))
      (node (ref "O4") (pin "2") (pinfunction "CAT_2") (pintype "unspecified"))
      (node (ref "O5") (pin "2") (pinfunction "CAT_2") (pintype "unspecified"))
      (node (ref "O6") (pin "2") (pinfunction "CAT_2") (pintype "unspecified"))
      (node (ref "Q1") (pin "2") (pinfunction "E_2") (pintype "input"))
      (node (ref "Q2") (pin "2") (pinfunction "E_2") (pintype "input"))
      (node (ref "Q3") (pin "2") (pinfunction "E_2") (pintype "input"))
      (node (ref "Q4") (pin "2") (pinfunction "E_2") (pintype "input"))
      (node (ref "Q5") (pin "2") (pinfunction "S_2") (pintype "unspecified"))
      (node (ref "Q6") (pin "2") (pinfunction "E_2") (pintype "input"))
      (node (ref "R19") (pin "1") (pinfunction "1_1") (pintype "unspecified"))
      (node (ref "R24") (pin "1") (pinfunction "1_1") (pintype "unspecified"))
      (node (ref "R28") (pin "1") (pinfunction "1_1") (pintype "unspecified"))
      (node (ref "R32") (pin "2") (pinfunction "2_2") (pintype "unspecified"))
      (node (ref "R34") (pin "1") (pinfunction "1_1") (pintype "unspecified"))
      (node (ref "R9") (pin "1") (pinfunction "1_1") (pintype "unspecified"))
      (node (ref "U1") (pin "2") (pinfunction "IN-_2") (pintype "passive"))
      (node (ref "U1") (pin "3") (pinfunction "OUT-_3") (pintype "passive"))
      (node (ref "U2") (pin "4") (pinfunction "GND_4") (pintype "unspecified"))
    )
    (net (code "19") (name "I_charge_max") (class "Default")
      (node (ref "J14") (pin "4") (pinfunction "4_4") (pintype "unspecified"))
      (node (ref "J21") (pin "14") (pinfunction "14_14") (pintype "unspecified"))
      (node (ref "M1") (pin "27") (pinfunction "PA2_27") (pintype "unspecified"))
    )
    (net (code "20") (name "I_discharge_max") (class "Default")
      (node (ref "J14") (pin "2") (pinfunction "2_2") (pintype "unspecified"))
      (node (ref "J21") (pin "16") (pinfunction "16_16") (pintype "unspecified"))
      (node (ref "M1") (pin "25") (pinfunction "PA0_25") (pintype "unspecified"))
    )
    (net (code "21") (name "LCD_Mode") (class "Default")
      (node (ref "J21") (pin "18") (pinfunction "18_18") (pintype "unspecified"))
      (node (ref "J6") (pin "2") (pinfunction "2_2") (pintype "unspecified"))
      (node (ref "M1") (pin "23") (pinfunction "PC14_23") (pintype "unspecified"))
    )
    (net (code "22") (name "LOAD") (class "Default")
      (node (ref "J21") (pin "17") (pinfunction "17_17") (pintype "unspecified"))
      (node (ref "J7") (pin "2") (pinfunction "2_2") (pintype "unspecified"))
      (node (ref "M1") (pin "24") (pinfunction "PC15_24") (pintype "unspecified"))
    )
    (net (code "23") (name "Monitoring") (class "Default")
      (node (ref "J22") (pin "11") (pinfunction "11_11") (pintype "unspecified"))
      (node (ref "J9") (pin "2") (pinfunction "2_2") (pintype "unspecified"))
      (node (ref "M1") (pin "10") (pinfunction "PA15_10") (pintype "unspecified"))
    )
    (net (code "24") (name "Net-(D2-Pad1)") (class "Default")
      (node (ref "D2") (pin "1") (pinfunction "1_1") (pintype "unspecified"))
      (node (ref "J3") (pin "2") (pinfunction "2_2") (pintype "unspecified"))
    )
    (net (code "25") (name "Net-(D3-Pad1)") (class "Default")
      (node (ref "D3") (pin "1") (pinfunction "1_1") (pintype "unspecified"))
      (node (ref "J4") (pin "1") (pinfunction "1_1") (pintype "unspecified"))
    )
    (net (code "26") (name "Net-(D6-A)") (class "Default")
      (node (ref "D6") (pin "2") (pinfunction "A_2") (pintype "unspecified"))
      (node (ref "J17") (pin "1") (pinfunction "1_1") (pintype "unspecified"))
      (node (ref "R10") (pin "2") (pinfunction "2_2") (pintype "unspecified"))
      (node (ref "R13") (pin "2") (pinfunction "2_2") (pintype "unspecified"))
    )
    (net (code "27") (name "Net-(D6-C)") (class "Default")
      (node (ref "D6") (pin "1") (pinfunction "C_1") (pintype "unspecified"))
      (node (ref "K1") (pin "5") (pinfunction "5_5") (pintype "unspecified"))
    )
    (net (code "28") (name "Net-(D10-Pad1)") (class "Default")
      (node (ref "D10") (pin "1") (pinfunction "1_1") (pintype "unspecified"))
      (node (ref "J20") (pin "1") (pinfunction "1_1") (pintype "unspecified"))
    )
    (net (code "29") (name "Net-(K2-Pad5)") (class "Default")
      (node (ref "K2") (pin "5") (pinfunction "5_5") (pintype "unspecified"))
      (node (ref "R20") (pin "1") (pinfunction "1_1") (pintype "unspecified"))
    )
    (net (code "30") (name "Net-(LD1-A)") (class "Default")
      (node (ref "LD1") (pin "2") (pinfunction "A_2") (pintype "unspecified"))
      (node (ref "R1") (pin "1") (pinfunction "1_1") (pintype "unspecified"))
    )
    (net (code "31") (name "Net-(LD2-A)") (class "Default")
      (node (ref "LD2") (pin "2") (pinfunction "A_2") (pintype "unspecified"))
      (node (ref "R2") (pin "2") (pinfunction "2_2") (pintype "unspecified"))
    )
    (net (code "32") (name "Net-(LD3-A)") (class "Default")
      (node (ref "LD3") (pin "2") (pinfunction "A_2") (pintype "unspecified"))
      (node (ref "R3") (pin "1") (pinfunction "1_1") (pintype "unspecified"))
    )
    (net (code "33") (name "Net-(LD4-A)") (class "Default")
      (node (ref "LD4") (pin "2") (pinfunction "A_2") (pintype "unspecified"))
      (node (ref "R4") (pin "1") (pinfunction "1_1") (pintype "unspecified"))
    )
    (net (code "34") (name "Net-(LD5-A)") (class "Default")
      (node (ref "LD5") (pin "2") (pinfunction "A_2") (pintype "unspecified"))
      (node (ref "R5") (pin "2") (pinfunction "2_2") (pintype "unspecified"))
    )
    (net (code "35") (name "Net-(LD6-A)") (class "Default")
      (node (ref "LD6") (pin "2") (pinfunction "A_2") (pintype "unspecified"))
      (node (ref "R6") (pin "1") (pinfunction "1_1") (pintype "unspecified"))
    )
    (net (code "36") (name "Net-(LD7-A)") (class "Default")
      (node (ref "LD7") (pin "2") (pinfunction "A_2") (pintype "unspecified"))
      (node (ref "R15") (pin "1") (pinfunction "1_1") (pintype "unspecified"))
    )
    (net (code "37") (name "Net-(LD8-A)") (class "Default")
      (node (ref "LD8") (pin "2") (pinfunction "A_2") (pintype "unspecified"))
      (node (ref "R16") (pin "1") (pinfunction "1_1") (pintype "unspecified"))
    )
    (net (code "38") (name "Net-(LD9-A)") (class "Default")
      (node (ref "LD9") (pin "2") (pinfunction "A_2") (pintype "unspecified"))
      (node (ref "R21") (pin "1") (pinfunction "1_1") (pintype "unspecified"))
    )
    (net (code "39") (name "Net-(LD10-A)") (class "Default")
      (node (ref "LD10") (pin "2") (pinfunction "A_2") (pintype "unspecified"))
      (node (ref "R25") (pin "1") (pinfunction "1_1") (pintype "unspecified"))
    )
    (net (code "40") (name "Net-(LD11-A)") (class "Default")
      (node (ref "LD11") (pin "2") (pinfunction "A_2") (pintype "unspecified"))
      (node (ref "R29") (pin "1") (pinfunction "1_1") (pintype "unspecified"))
    )
    (net (code "41") (name "Net-(M1-+5V)") (class "Default")
      (node (ref "J20") (pin "2") (pinfunction "2_2") (pintype "unspecified"))
      (node (ref "J22") (pin "3") (pinfunction "3_3") (pintype "unspecified"))
      (node (ref "M1") (pin "18") (pinfunction "+5V_18") (pintype "unspecified"))
    )
    (net (code "42") (name "Net-(M1-PA6)") (class "Default")
      (node (ref "J21") (pin "10") (pinfunction "10_10") (pintype "unspecified"))
      (node (ref "M1") (pin "31") (pinfunction "PA6_31") (pintype "unspecified"))
    )
    (net (code "43") (name "Net-(M1-PA7)") (class "Default")
      (node (ref "J21") (pin "9") (pinfunction "9_9") (pintype "unspecified"))
      (node (ref "M1") (pin "32") (pinfunction "PA7_32") (pintype "unspecified"))
    )
    (net (code "44") (name "Net-(M1-PA11)") (class "Default")
      (node (ref "J22") (pin "13") (pinfunction "13_13") (pintype "unspecified"))
      (node (ref "M1") (pin "8") (pinfunction "PA11_8") (pintype "unspecified"))
    )
    (net (code "45") (name "Net-(M1-PA12)") (class "Default")
      (node (ref "J22") (pin "12") (pinfunction "12_12") (pintype "unspecified"))
      (node (ref "M1") (pin "9") (pinfunction "PA12_9") (pintype "unspecified"))
    )
    (net (code "46") (name "Net-(M1-PB0)") (class "Default")
      (node (ref "J21") (pin "8") (pinfunction "8_8") (pintype "unspecified"))
      (node (ref "M1") (pin "33") (pinfunction "PB0_33") (pintype "unspecified"))
    )
    (net (code "47") (name "Net-(M1-PB12)") (class "Default")
      (node (ref "J22") (pin "20") (pinfunction "20_20") (pintype "unspecified"))
      (node (ref "M1") (pin "1") (pinfunction "PB12_1") (pintype "unspecified"))
    )
    (net (code "48") (name "Net-(M1-PB13)") (class "Default")
      (node (ref "J22") (pin "19") (pinfunction "19_19") (pintype "unspecified"))
      (node (ref "M1") (pin "2") (pinfunction "PB13_2") (pintype "unspecified"))
    )
    (net (code "49") (name "Net-(M1-PC13)") (class "Default")
      (node (ref "J21") (pin "19") (pinfunction "19_19") (pintype "unspecified"))
      (node (ref "M1") (pin "22") (pinfunction "PC13_22") (pintype "unspecified"))
    )
    (net (code "50") (name "Net-(M1-RESET)") (class "Default")
      (node (ref "J21") (pin "4") (pinfunction "4_4") (pintype "unspecified"))
      (node (ref "M1") (pin "37") (pinfunction "RESET_37") (pintype "unspecified"))
    )
    (net (code "51") (name "Net-(M1-VBAT)") (class "Default")
      (node (ref "J21") (pin "20") (pinfunction "20_20") (pintype "unspecified"))
      (node (ref "M1") (pin "21") (pinfunction "VBAT_21") (pintype "unspecified"))
    )
    (net (code "52") (name "Net-(O1-AN)") (class "Default")
      (node (ref "O1") (pin "1") (pinfunction "AN_1") (pintype "unspecified"))
      (node (ref "R7") (pin "1") (pinfunction "1_1") (pintype "unspecified"))
    )
    (net (code "53") (name "Net-(O1-EM)") (class "Default")
      (node (ref "O1") (pin "3") (pinfunction "EM_3") (pintype "unspecified"))
      (node (ref "R8") (pin "2") (pinfunction "2_2") (pintype "unspecified"))
    )
    (net (code "54") (name "Net-(O2-AN)") (class "Default")
      (node (ref "O2") (pin "1") (pinfunction "AN_1") (pintype "unspecified"))
      (node (ref "R12") (pin "1") (pinfunction "1_1") (pintype "unspecified"))
    )
    (net (code "55") (name "Net-(O3-AN)") (class "Default")
      (node (ref "O3") (pin "1") (pinfunction "AN_1") (pintype "unspecified"))
      (node (ref "R17") (pin "1") (pinfunction "1_1") (pintype "unspecified"))
    )
    (net (code "56") (name "Net-(O3-EM)") (class "Default")
      (node (ref "O3") (pin "3") (pinfunction "EM_3") (pintype "unspecified"))
      (node (ref "R18") (pin "2") (pinfunction "2_2") (pintype "unspecified"))
    )
    (net (code "57") (name "Net-(O4-AN)") (class "Default")
      (node (ref "O4") (pin "1") (pinfunction "AN_1") (pintype "unspecified"))
      (node (ref "R22") (pin "1") (pinfunction "1_1") (pintype "unspecified"))
    )
    (net (code "58") (name "Net-(O4-EM)") (class "Default")
      (node (ref "O4") (pin "3") (pinfunction "EM_3") (pintype "unspecified"))
      (node (ref "R23") (pin "2") (pinfunction "2_2") (pintype "unspecified"))
    )
    (net (code "59") (name "Net-(O5-AN)") (class "Default")
      (node (ref "O5") (pin "1") (pinfunction "AN_1") (pintype "unspecified"))
      (node (ref "R26") (pin "1") (pinfunction "1_1") (pintype "unspecified"))
    )
    (net (code "60") (name "Net-(O5-EM)") (class "Default")
      (node (ref "O5") (pin "3") (pinfunction "EM_3") (pintype "unspecified"))
      (node (ref "R27") (pin "2") (pinfunction "2_2") (pintype "unspecified"))
    )
    (net (code "61") (name "Net-(O6-AN)") (class "Default")
      (node (ref "O6") (pin "1") (pinfunction "AN_1") (pintype "unspecified"))
      (node (ref "R30") (pin "1") (pinfunction "1_1") (pintype "unspecified"))
    )
    (net (code "62") (name "Net-(O6-EM)") (class "Default")
      (node (ref "O6") (pin "3") (pinfunction "EM_3") (pintype "unspecified"))
      (node (ref "R31") (pin "1") (pinfunction "1_1") (pintype "unspecified"))
    )
    (net (code "63") (name "Net-(Q1-B)") (class "Default")
      (node (ref "Q1") (pin "1") (pinfunction "B_1") (pintype "input"))
      (node (ref "R8") (pin "1") (pinfunction "1_1") (pintype "unspecified"))
      (node (ref "R9") (pin "2") (pinfunction "2_2") (pintype "unspecified"))
    )
    (net (code "64") (name "Net-(Q1-C)") (class "Default")
      (node (ref "D5") (pin "2") (pinfunction "2_2") (pintype "unspecified"))
      (node (ref "K1") (pin "4") (pinfunction "4_4") (pintype "unspecified"))
      (node (ref "Q1") (pin "3") (pinfunction "C_3") (pintype "input"))
    )
    (net (code "65") (name "Net-(Q2-B)") (class "Default")
      (node (ref "Q2") (pin "1") (pinfunction "B_1") (pintype "input"))
      (node (ref "R18") (pin "1") (pinfunction "1_1") (pintype "unspecified"))
      (node (ref "R19") (pin "2") (pinfunction "2_2") (pintype "unspecified"))
    )
    (net (code "66") (name "Net-(Q2-C)") (class "Default")
      (node (ref "D7") (pin "2") (pinfunction "2_2") (pintype "unspecified"))
      (node (ref "K2") (pin "4") (pinfunction "4_4") (pintype "unspecified"))
      (node (ref "Q2") (pin "3") (pinfunction "C_3") (pintype "input"))
    )
    (net (code "67") (name "Net-(Q3-B)") (class "Default")
      (node (ref "Q3") (pin "1") (pinfunction "B_1") (pintype "input"))
      (node (ref "R23") (pin "1") (pinfunction "1_1") (pintype "unspecified"))
      (node (ref "R24") (pin "2") (pinfunction "2_2") (pintype "unspecified"))
    )
    (net (code "68") (name "Net-(Q3-C)") (class "Default")
      (node (ref "D8") (pin "2") (pinfunction "2_2") (pintype "unspecified"))
      (node (ref "K3") (pin "4") (pinfunction "4_4") (pintype "unspecified"))
      (node (ref "Q3") (pin "3") (pinfunction "C_3") (pintype "input"))
    )
    (net (code "69") (name "Net-(Q4-B)") (class "Default")
      (node (ref "Q4") (pin "1") (pinfunction "B_1") (pintype "input"))
      (node (ref "R27") (pin "1") (pinfunction "1_1") (pintype "unspecified"))
      (node (ref "R28") (pin "2") (pinfunction "2_2") (pintype "unspecified"))
    )
    (net (code "70") (name "Net-(Q4-C)") (class "Default")
      (node (ref "D9") (pin "2") (pinfunction "2_2") (pintype "unspecified"))
      (node (ref "K4") (pin "4") (pinfunction "4_4") (pintype "unspecified"))
      (node (ref "Q4") (pin "3") (pinfunction "C_3") (pintype "input"))
    )
    (net (code "71") (name "Net-(Q5-D)") (class "Default")
      (node (ref "J18") (pin "2") (pinfunction "2_2") (pintype "unspecified"))
      (node (ref "J19") (pin "2") (pinfunction "2_2") (pintype "unspecified"))
      (node (ref "Q5") (pin "3") (pinfunction "D_3") (pintype "unspecified"))
    )
    (net (code "72") (name "Net-(Q5-G)") (class "Default")
      (node (ref "Q5") (pin "1") (pinfunction "G_1") (pintype "unspecified"))
      (node (ref "R31") (pin "2") (pinfunction "2_2") (pintype "unspecified"))
      (node (ref "R32") (pin "1") (pinfunction "1_1") (pintype "unspecified"))
    )
    (net (code "73") (name "Net-(Q6-B)") (class "Default")
      (node (ref "Q6") (pin "1") (pinfunction "B_1") (pintype "input"))
      (node (ref "R33") (pin "1") (pinfunction "1_1") (pintype "unspecified"))
      (node (ref "R34") (pin "2") (pinfunction "2_2") (pintype "unspecified"))
    )
    (net (code "74") (name "Net-(Q6-C)") (class "Default")
      (node (ref "BZ1") (pin "2") (pinfunction "2_2") (pintype "unspecified"))
      (node (ref "Q6") (pin "3") (pinfunction "C_3") (pintype "input"))
    )
    (net (code "75") (name "Net-(R10-Pad1)") (class "Default")
      (node (ref "R10") (pin "1") (pinfunction "1_1") (pintype "unspecified"))
      (node (ref "R11") (pin "2") (pinfunction "2_2") (pintype "unspecified"))
    )
    (net (code "76") (name "Net-(R11-Pad1)") (class "Default")
      (node (ref "R11") (pin "1") (pinfunction "1_1") (pintype "unspecified"))
      (node (ref "R12") (pin "2") (pinfunction "2_2") (pintype "unspecified"))
    )
    (net (code "77") (name "Net-(R13-Pad1)") (class "Default")
      (node (ref "R13") (pin "1") (pinfunction "1_1") (pintype "unspecified"))
      (node (ref "R14") (pin "2") (pinfunction "2_2") (pintype "unspecified"))
    )
    (net (code "78") (name "Net-(R14-Pad1)") (class "Default")
      (node (ref "R14") (pin "1") (pinfunction "1_1") (pintype "unspecified"))
      (node (ref "R15") (pin "2") (pinfunction "2_2") (pintype "unspecified"))
    )
    (net (code "79") (name "Net-(U1-IN+)") (class "Default")
      (node (ref "D1") (pin "1") (pinfunction "1_1") (pintype "unspecified"))
      (node (ref "F1") (pin "2") (pinfunction "2_2") (pintype "unspecified"))
      (node (ref "R1") (pin "2") (pinfunction "2_2") (pintype "unspecified"))
      (node (ref "U1") (pin "1") (pinfunction "IN+_1") (pintype "passive"))
    )
    (net (code "80") (name "Net-(U1-OUT+)") (class "Default")
      (node (ref "J2") (pin "2") (pinfunction "2_2") (pintype "unspecified"))
      (node (ref "U1") (pin "4") (pinfunction "OUT+_4") (pintype "passive"))
    )
    (net (code "81") (name "Net-(U2-CANH)") (class "Default")
      (node (ref "J5") (pin "2") (pinfunction "2_2") (pintype "unspecified"))
      (node (ref "U2") (pin "6") (pinfunction "CANH_6") (pintype "unspecified"))
    )
    (net (code "82") (name "Net-(U2-CANL)") (class "Default")
      (node (ref "J5") (pin "1") (pinfunction "1_1") (pintype "unspecified"))
      (node (ref "U2") (pin "5") (pinfunction "CANL_5") (pintype "unspecified"))
    )
    (net (code "83") (name "Net-(U2-VCC)") (class "Default")
      (node (ref "D4") (pin "1") (pinfunction "1_1") (pintype "unspecified"))
      (node (ref "U2") (pin "1") (pinfunction "VCC_1") (pintype "unspecified"))
    )
    (net (code "84") (name "Precharge_Control") (class "Default")
      (node (ref "J21") (pin "7") (pinfunction "7_7") (pintype "unspecified"))
      (node (ref "M1") (pin "34") (pinfunction "PB1_34") (pintype "unspecified"))
      (node (ref "R16") (pin "2") (pinfunction "2_2") (pintype "unspecified"))
      (node (ref "R17") (pin "2") (pinfunction "2_2") (pintype "unspecified"))
    )
    (net (code "85") (name "RX") (class "Default")
      (node (ref "J11") (pin "2") (pinfunction "2_2") (pintype "unspecified"))
      (node (ref "J22") (pin "14") (pinfunction "14_14") (pintype "unspecified"))
      (node (ref "M1") (pin "7") (pinfunction "PA10_7") (pintype "unspecified"))
    )
    (net (code "86") (name "SCL") (class "Default")
      (node (ref "J22") (pin "7") (pinfunction "7_7") (pintype "unspecified"))
      (node (ref "J3") (pin "4") (pinfunction "4_4") (pintype "unspecified"))
      (node (ref "M1") (pin "14") (pinfunction "PB6_14") (pintype "unspecified"))
    )
    (net (code "87") (name "SDA") (class "Default")
      (node (ref "J22") (pin "6") (pinfunction "6_6") (pintype "unspecified"))
      (node (ref "J3") (pin "3") (pinfunction "3_3") (pintype "unspecified"))
      (node (ref "M1") (pin "15") (pinfunction "PB7_15") (pintype "unspecified"))
    )
    (net (code "88") (name "SW_ButtonLeft") (class "Default")
      (node (ref "J12") (pin "2") (pinfunction "2_2") (pintype "unspecified"))
      (node (ref "J22") (pin "16") (pinfunction "16_16") (pintype "unspecified"))
      (node (ref "M1") (pin "5") (pinfunction "PA8_5") (pintype "unspecified"))
    )
    (net (code "89") (name "SW_ButtonRight") (class "Default")
      (node (ref "J13") (pin "2") (pinfunction "2_2") (pintype "unspecified"))
      (node (ref "J22") (pin "9") (pinfunction "9_9") (pintype "unspecified"))
      (node (ref "M1") (pin "12") (pinfunction "PB4_12") (pintype "unspecified"))
    )
    (net (code "90") (name "TX") (class "Default")
      (node (ref "J11") (pin "3") (pinfunction "3_3") (pintype "unspecified"))
      (node (ref "J22") (pin "15") (pinfunction "15_15") (pintype "unspecified"))
      (node (ref "M1") (pin "6") (pinfunction "PA9_6") (pintype "unspecified"))
    )
    (net (code "91") (name "V_charge_max") (class "Default")
      (node (ref "J14") (pin "5") (pinfunction "5_5") (pintype "unspecified"))
      (node (ref "J21") (pin "13") (pinfunction "13_13") (pintype "unspecified"))
      (node (ref "M1") (pin "28") (pinfunction "PA3_28") (pintype "unspecified"))
    )
    (net (code "92") (name "V_discharge_min") (class "Default")
      (node (ref "J14") (pin "3") (pinfunction "3_3") (pintype "unspecified"))
      (node (ref "J21") (pin "15") (pinfunction "15_15") (pintype "unspecified"))
      (node (ref "M1") (pin "26") (pinfunction "PA1_26") (pintype "unspecified"))
    )
    (net (code "93") (name "unconnected-(H1-Pad1)") (class "Default")
      (node (ref "H1") (pin "1") (pinfunction "1_1") (pintype "unspecified+no_connect"))
    )
    (net (code "94") (name "unconnected-(H2-Pad1)") (class "Default")
      (node (ref "H2") (pin "1") (pinfunction "1_1") (pintype "unspecified+no_connect"))
    )
    (net (code "95") (name "unconnected-(H3-Pad1)") (class "Default")
      (node (ref "H3") (pin "1") (pinfunction "1_1") (pintype "unspecified+no_connect"))
    )
    (net (code "96") (name "unconnected-(H4-Pad1)") (class "Default")
      (node (ref "H4") (pin "1") (pinfunction "1_1") (pintype "unspecified+no_connect"))
    )
    (net (code "97") (name "unconnected-(J4-Pad2)") (class "Default")
      (node (ref "J4") (pin "2") (pinfunction "2_2") (pintype "unspecified+no_connect"))
    )
    (net (code "98") (name "unconnected-(J11-Pad1)") (class "Default")
      (node (ref "J11") (pin "1") (pinfunction "1_1") (pintype "unspecified"))
    )
    (net (code "99") (name "unconnected-(K1-Pad1)") (class "Default")
      (node (ref "K1") (pin "1") (pinfunction "1_1") (pintype "unspecified"))
    )
    (net (code "100") (name "unconnected-(K2-Pad2)") (class "Default")
      (node (ref "K2") (pin "2") (pinfunction "2_2") (pintype "unspecified"))
    )
  )
)
